# CABLE_MOTOR_DRIVERS.net
KiCad netlist of a schematic drawn in Altium Designer
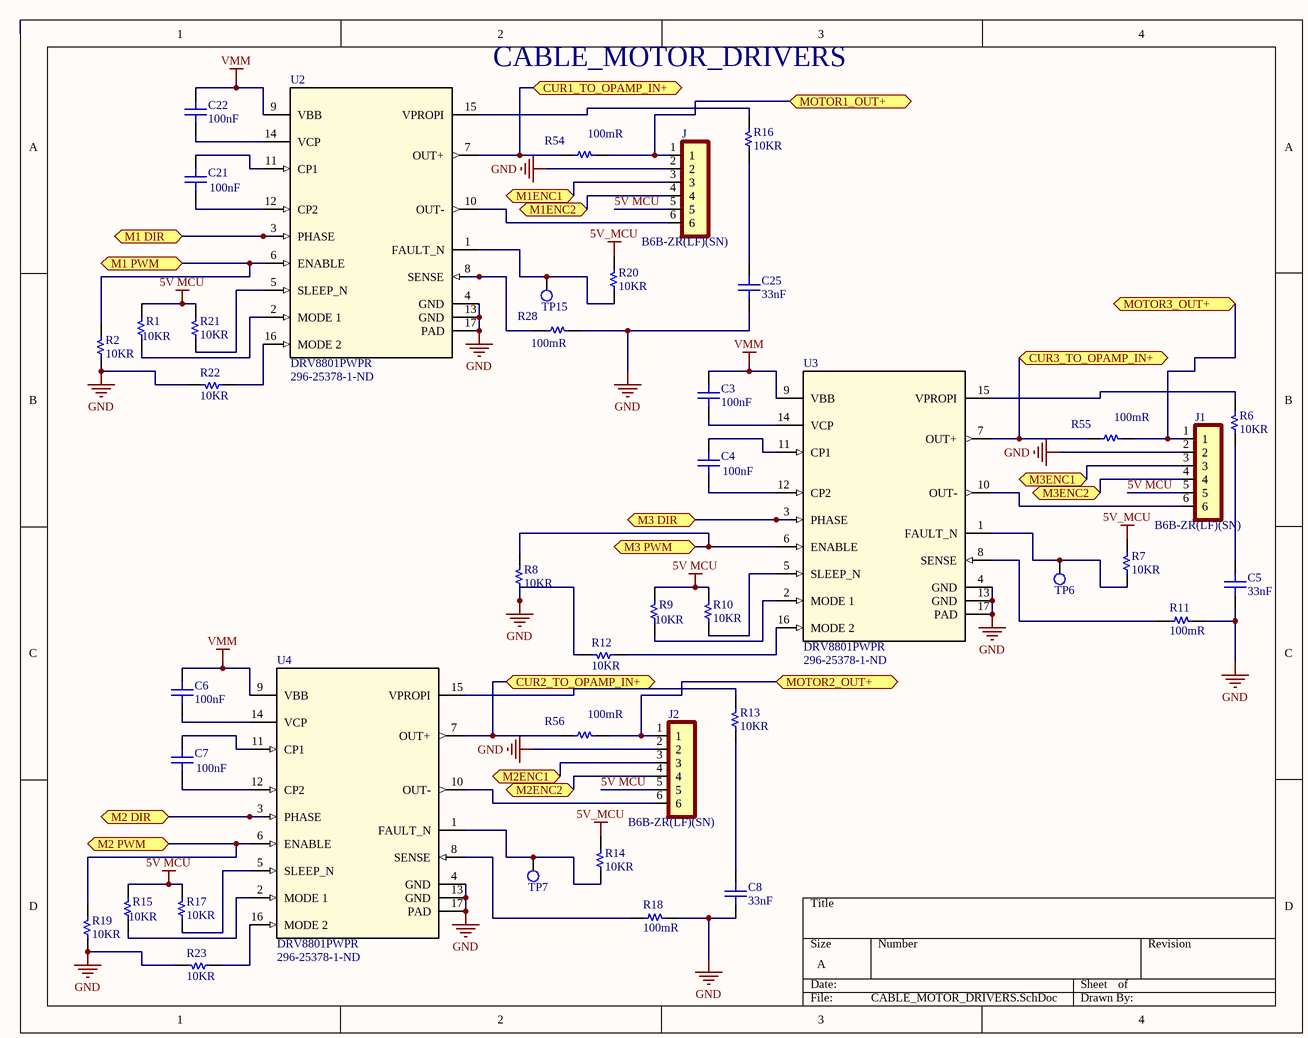
[diagram p0: CABLE_MOTOR_DRIVERS.SchDoc]

(export (version "E")
  (design (tool "Eeschema 10.0.6"))
  (components
    (comp (ref "C3")
      (value "100nF")
      (footprint "CAP_ADJ_0805")
      (description "CERAMIC CAPACITOR SMD 0805")
      (fields
        (field (name "MANUFACTURER") "KEMET")
        (field (name "MANUFACTURER PART NUMBER") "C0805C104J5RACAUTO")
      )
      (libsource (lib "ORI_MANIPULATOR_BRD") (part "CAP_ADJ_0805"))
    )
    (comp (ref "C4")
      (value "100nF")
      (footprint "CAP_ADJ_0805")
      (description "CERAMIC CAPACITOR SMD 0805")
      (fields
        (field (name "MANUFACTURER") "KEMET")
        (field (name "MANUFACTURER PART NUMBER") "C0805C104J5RACAUTO")
      )
      (libsource (lib "ORI_MANIPULATOR_BRD") (part "CAP_ADJ_0805"))
    )
    (comp (ref "C5")
      (value "33nF")
      (footprint "CAP_ADJ_0805")
      (description "CERAMIC CAPACITOR SMD 0805")
      (fields
        (field (name "MANUFACTURER") "Samsung")
        (field (name "MANUFACTURER PART NUMBER") "CL21B333JBANNNC")
      )
      (libsource (lib "ORI_MANIPULATOR_BRD") (part "CAP_ADJ_0805"))
    )
    (comp (ref "C6")
      (value "100nF")
      (footprint "CAP_ADJ_0805")
      (description "CERAMIC CAPACITOR SMD 0805")
      (fields
        (field (name "MANUFACTURER") "KEMET")
        (field (name "MANUFACTURER PART NUMBER") "C0805C104J5RACAUTO")
      )
      (libsource (lib "ORI_MANIPULATOR_BRD") (part "CAP_ADJ_0805"))
    )
    (comp (ref "C7")
      (value "100nF")
      (footprint "CAP_ADJ_0805")
      (description "CERAMIC CAPACITOR SMD 0805")
      (fields
        (field (name "MANUFACTURER") "KEMET")
        (field (name "MANUFACTURER PART NUMBER") "C0805C104J5RACAUTO")
      )
      (libsource (lib "ORI_MANIPULATOR_BRD") (part "CAP_ADJ_0805"))
    )
    (comp (ref "C8")
      (value "33nF")
      (footprint "CAP_ADJ_0805")
      (description "CERAMIC CAPACITOR SMD 0805")
      (fields
        (field (name "MANUFACTURER") "Samsung")
        (field (name "MANUFACTURER PART NUMBER") "CL21B333JBANNNC")
      )
      (libsource (lib "ORI_MANIPULATOR_BRD") (part "CAP_ADJ_0805"))
    )
    (comp (ref "C21")
      (value "100nF")
      (footprint "CAP_ADJ_0805")
      (description "CERAMIC CAPACITOR SMD 0805")
      (fields
        (field (name "MANUFACTURER") "KEMET")
        (field (name "MANUFACTURER PART NUMBER") "C0805C104J5RACAUTO")
      )
      (libsource (lib "ORI_MANIPULATOR_BRD") (part "CAP_ADJ_0805"))
    )
    (comp (ref "C22")
      (value "100nF")
      (footprint "CAP_ADJ_0805")
      (description "CERAMIC CAPACITOR SMD 0805")
      (fields
        (field (name "MANUFACTURER") "KEMET")
        (field (name "MANUFACTURER PART NUMBER") "C0805C104J5RACAUTO")
      )
      (libsource (lib "ORI_MANIPULATOR_BRD") (part "CAP_ADJ_0805"))
    )
    (comp (ref "C25")
      (value "33nF")
      (footprint "CAP_ADJ_0805")
      (description "CERAMIC CAPACITOR SMD 0805")
      (fields
        (field (name "MANUFACTURER") "Samsung")
        (field (name "MANUFACTURER PART NUMBER") "CL21B333JBANNNC")
      )
      (libsource (lib "ORI_MANIPULATOR_BRD") (part "CAP_ADJ_0805"))
    )
    (comp (ref "J")
      (value "B6B-ZR(LF)(SN)")
      (footprint "SnapEDApcb:JST_B6B-ZR(LF)(SN)")
      (description "Connector Header Through Hole 6 position 0.059 _1.50mm_")
      (fields (field (name "MF") "JST Sales") (field (name "MP") "B6B-ZR_LF__SN_"))
      (libsource (lib "SnapEDAsch") (part "B6B-ZR(LF)(SN)"))
    )
    (comp (ref "J1")
      (value "B6B-ZR(LF)(SN)")
      (footprint "SnapEDApcb:JST_B6B-ZR(LF)(SN)")
      (description "Connector Header Through Hole 6 position 0.059 _1.50mm_")
      (fields (field (name "MF") "JST Sales") (field (name "MP") "B6B-ZR_LF__SN_"))
      (libsource (lib "SnapEDAsch") (part "B6B-ZR(LF)(SN)"))
    )
    (comp (ref "J2")
      (value "B6B-ZR(LF)(SN)")
      (footprint "SnapEDApcb:JST_B6B-ZR(LF)(SN)")
      (description "Connector Header Through Hole 6 position 0.059 _1.50mm_")
      (fields (field (name "MF") "JST Sales") (field (name "MP") "B6B-ZR_LF__SN_"))
      (libsource (lib "SnapEDAsch") (part "B6B-ZR(LF)(SN)"))
    )
    (comp (ref "R1")
      (value "10KR")
      (footprint "RES_ADJ_0805_YAGEO")
      (description "RESISTOR 0805 YAGEO")
      (fields
        (field (name "MANUFACTURER") "Yageo")
        (field (name "MANUFACTURER PART NUMBER") "RC0805JR-0710KL")
      )
      (libsource (lib "ORI_MANIPULATOR_BRD") (part "RES_ADJ_0805"))
    )
    (comp (ref "R2")
      (value "10KR")
      (footprint "RES_ADJ_0805_YAGEO")
      (description "RESISTOR 0805 YAGEO")
      (fields
        (field (name "MANUFACTURER") "Yageo")
        (field (name "MANUFACTURER PART NUMBER") "RC0805JR-0710KL")
      )
      (libsource (lib "ORI_MANIPULATOR_BRD") (part "RES_ADJ_0805"))
    )
    (comp (ref "R6")
      (value "10KR")
      (footprint "RES_ADJ_0805_YAGEO")
      (description "RESISTOR 0805 YAGEO")
      (fields
        (field (name "MANUFACTURER") "Yageo")
        (field (name "MANUFACTURER PART NUMBER") "RC0805JR-0710KL")
      )
      (libsource (lib "ORI_MANIPULATOR_BRD") (part "RES_ADJ_0805"))
    )
    (comp (ref "R7")
      (value "10KR")
      (footprint "RES_ADJ_0805_YAGEO")
      (description "RESISTOR 0805 YAGEO")
      (fields
        (field (name "MANUFACTURER") "Yageo")
        (field (name "MANUFACTURER PART NUMBER") "RC0805JR-0710KL")
      )
      (libsource (lib "ORI_MANIPULATOR_BRD") (part "RES_ADJ_0805"))
    )
    (comp (ref "R8")
      (value "10KR")
      (footprint "RES_ADJ_0805_YAGEO")
      (description "RESISTOR 0805 YAGEO")
      (fields
        (field (name "MANUFACTURER") "Yageo")
        (field (name "MANUFACTURER PART NUMBER") "RC0805JR-0710KL")
      )
      (libsource (lib "ORI_MANIPULATOR_BRD") (part "RES_ADJ_0805"))
    )
    (comp (ref "R9")
      (value "10KR")
      (footprint "RES_ADJ_0805_YAGEO")
      (description "RESISTOR 0805 YAGEO")
      (fields
        (field (name "MANUFACTURER") "Yageo")
        (field (name "MANUFACTURER PART NUMBER") "RC0805JR-0710KL")
      )
      (libsource (lib "ORI_MANIPULATOR_BRD") (part "RES_ADJ_0805"))
    )
    (comp (ref "R10")
      (value "10KR")
      (footprint "RES_ADJ_0805_YAGEO")
      (description "RESISTOR 0805 YAGEO")
      (fields
        (field (name "MANUFACTURER") "Yageo")
        (field (name "MANUFACTURER PART NUMBER") "RC0805JR-0710KL")
      )
      (libsource (lib "ORI_MANIPULATOR_BRD") (part "RES_ADJ_0805"))
    )
    (comp (ref "R11")
      (value "100mR")
      (footprint "RES_ADJ_0805_YAGEO")
      (description "RESISTOR 0805 YAGEO")
      (fields
        (field (name "MANUFACTURER") "Panasonic")
        (field (name "MANUFACTURER PART NUMBER") "ERJ-6DSFR10V")
      )
      (libsource (lib "ORI_MANIPULATOR_BRD") (part "RES_ADJ_0805"))
    )
    (comp (ref "R12")
      (value "10KR")
      (footprint "RES_ADJ_0805_YAGEO")
      (description "RESISTOR 0805 YAGEO")
      (fields
        (field (name "MANUFACTURER") "Yageo")
        (field (name "MANUFACTURER PART NUMBER") "RC0805JR-0710KL")
      )
      (libsource (lib "ORI_MANIPULATOR_BRD") (part "RES_ADJ_0805"))
    )
    (comp (ref "R13")
      (value "10KR")
      (footprint "RES_ADJ_0805_YAGEO")
      (description "RESISTOR 0805 YAGEO")
      (fields
        (field (name "MANUFACTURER") "Yageo")
        (field (name "MANUFACTURER PART NUMBER") "RC0805JR-0710KL")
      )
      (libsource (lib "ORI_MANIPULATOR_BRD") (part "RES_ADJ_0805"))
    )
    (comp (ref "R14")
      (value "10KR")
      (footprint "RES_ADJ_0805_YAGEO")
      (description "RESISTOR 0805 YAGEO")
      (fields
        (field (name "MANUFACTURER") "Yageo")
        (field (name "MANUFACTURER PART NUMBER") "RC0805JR-0710KL")
      )
      (libsource (lib "ORI_MANIPULATOR_BRD") (part "RES_ADJ_0805"))
    )
    (comp (ref "R15")
      (value "10KR")
      (footprint "RES_ADJ_0805_YAGEO")
      (description "RESISTOR 0805 YAGEO")
      (fields
        (field (name "MANUFACTURER") "Yageo")
        (field (name "MANUFACTURER PART NUMBER") "RC0805JR-0710KL")
      )
      (libsource (lib "ORI_MANIPULATOR_BRD") (part "RES_ADJ_0805"))
    )
    (comp (ref "R16")
      (value "10KR")
      (footprint "RES_ADJ_0805_YAGEO")
      (description "RESISTOR 0805 YAGEO")
      (fields
        (field (name "MANUFACTURER") "Yageo")
        (field (name "MANUFACTURER PART NUMBER") "RC0805JR-0710KL")
      )
      (libsource (lib "ORI_MANIPULATOR_BRD") (part "RES_ADJ_0805"))
    )
    (comp (ref "R17")
      (value "10KR")
      (footprint "RES_ADJ_0805_YAGEO")
      (description "RESISTOR 0805 YAGEO")
      (fields
        (field (name "MANUFACTURER") "Yageo")
        (field (name "MANUFACTURER PART NUMBER") "RC0805JR-0710KL")
      )
      (libsource (lib "ORI_MANIPULATOR_BRD") (part "RES_ADJ_0805"))
    )
    (comp (ref "R18")
      (value "100mR")
      (footprint "RES_ADJ_0805_YAGEO")
      (description "RESISTOR 0805 YAGEO")
      (fields
        (field (name "MANUFACTURER") "Panasonic")
        (field (name "MANUFACTURER PART NUMBER") "ERJ-6DSFR10V")
      )
      (libsource (lib "ORI_MANIPULATOR_BRD") (part "RES_ADJ_0805"))
    )
    (comp (ref "R19")
      (value "10KR")
      (footprint "RES_ADJ_0805_YAGEO")
      (description "RESISTOR 0805 YAGEO")
      (fields
        (field (name "MANUFACTURER") "Yageo")
        (field (name "MANUFACTURER PART NUMBER") "RC0805JR-0710KL")
      )
      (libsource (lib "ORI_MANIPULATOR_BRD") (part "RES_ADJ_0805"))
    )
    (comp (ref "R20")
      (value "10KR")
      (footprint "RES_ADJ_0805_YAGEO")
      (description "RESISTOR 0805 YAGEO")
      (fields
        (field (name "MANUFACTURER") "Yageo")
        (field (name "MANUFACTURER PART NUMBER") "RC0805JR-0710KL")
      )
      (libsource (lib "ORI_MANIPULATOR_BRD") (part "RES_ADJ_0805"))
    )
    (comp (ref "R21")
      (value "10KR")
      (footprint "RES_ADJ_0805_YAGEO")
      (description "RESISTOR 0805 YAGEO")
      (fields
        (field (name "MANUFACTURER") "Yageo")
        (field (name "MANUFACTURER PART NUMBER") "RC0805JR-0710KL")
      )
      (libsource (lib "ORI_MANIPULATOR_BRD") (part "RES_ADJ_0805"))
    )
    (comp (ref "R22")
      (value "10KR")
      (footprint "RES_ADJ_0805_YAGEO")
      (description "RESISTOR 0805 YAGEO")
      (fields
        (field (name "MANUFACTURER") "Yageo")
        (field (name "MANUFACTURER PART NUMBER") "RC0805JR-0710KL")
      )
      (libsource (lib "ORI_MANIPULATOR_BRD") (part "RES_ADJ_0805"))
    )
    (comp (ref "R23")
      (value "10KR")
      (footprint "RES_ADJ_0805_YAGEO")
      (description "RESISTOR 0805 YAGEO")
      (fields
        (field (name "MANUFACTURER") "Yageo")
        (field (name "MANUFACTURER PART NUMBER") "RC0805JR-0710KL")
      )
      (libsource (lib "ORI_MANIPULATOR_BRD") (part "RES_ADJ_0805"))
    )
    (comp (ref "R28")
      (value "100mR")
      (footprint "RES_ADJ_0805_YAGEO")
      (description "RESISTOR 0805 YAGEO")
      (fields
        (field (name "MANUFACTURER") "Panasonic")
        (field (name "MANUFACTURER PART NUMBER") "ERJ-6DSFR10V")
      )
      (libsource (lib "ORI_MANIPULATOR_BRD") (part "RES_ADJ_0805"))
    )
    (comp (ref "R54")
      (value "100mR")
      (footprint "RES_ADJ_0805_YAGEO")
      (description "RESISTOR 0805 YAGEO")
      (fields
        (field (name "MANUFACTURER") "Panasonic")
        (field (name "MANUFACTURER PART NUMBER") "ERJ-6DSFR10V")
      )
      (libsource (lib "ORI_MANIPULATOR_BRD") (part "RES_ADJ_0805"))
    )
    (comp (ref "R55")
      (value "100mR")
      (footprint "RES_ADJ_0805_YAGEO")
      (description "RESISTOR 0805 YAGEO")
      (fields
        (field (name "MANUFACTURER") "Panasonic")
        (field (name "MANUFACTURER PART NUMBER") "ERJ-6DSFR10V")
      )
      (libsource (lib "ORI_MANIPULATOR_BRD") (part "RES_ADJ_0805"))
    )
    (comp (ref "R56")
      (value "100mR")
      (footprint "RES_ADJ_0805_YAGEO")
      (description "RESISTOR 0805 YAGEO")
      (fields
        (field (name "MANUFACTURER") "Panasonic")
        (field (name "MANUFACTURER PART NUMBER") "ERJ-6DSFR10V")
      )
      (libsource (lib "ORI_MANIPULATOR_BRD") (part "RES_ADJ_0805"))
    )
    (comp (ref "TP6")
      (value "TEST_POINT")
      (footprint "TEST_POINT")
      (description "TEST POINT PAD")
      (libsource (lib "ORI_MANIPULATOR_BRD") (part "TEST_POINT"))
    )
    (comp (ref "TP7")
      (value "TEST_POINT")
      (footprint "TEST_POINT")
      (description "TEST POINT PAD")
      (libsource (lib "ORI_MANIPULATOR_BRD") (part "TEST_POINT"))
    )
    (comp (ref "TP15")
      (value "TEST_POINT")
      (footprint "TEST_POINT")
      (description "TEST POINT PAD")
      (libsource (lib "ORI_MANIPULATOR_BRD") (part "TEST_POINT"))
    )
    (comp (ref "U2")
      (value "DRV8801PWPR")
      (footprint "PWP0016B_N")
      (description "IC MOTOR DRIVER PAR 16HTSSOP")
      (fields
        (field (name "MANUFACTURER") "Texas Instruments")
        (field (name "SUPPLIER PART NUMBER 1") "296-25378-1-ND")
      )
      (libsource (lib "ORI_MANIPULATOR_BRD") (part "DRV8801PWPR"))
    )
    (comp (ref "U3")
      (value "DRV8801PWPR")
      (footprint "PWP0016B_N")
      (description "IC MOTOR DRIVER PAR 16HTSSOP")
      (fields
        (field (name "MANUFACTURER") "Texas Instruments")
        (field (name "SUPPLIER PART NUMBER 1") "296-25378-1-ND")
      )
      (libsource (lib "ORI_MANIPULATOR_BRD") (part "DRV8801PWPR"))
    )
    (comp (ref "U4")
      (value "DRV8801PWPR")
      (footprint "PWP0016B_N")
      (description "IC MOTOR DRIVER PAR 16HTSSOP")
      (fields
        (field (name "MANUFACTURER") "Texas Instruments")
        (field (name "SUPPLIER PART NUMBER 1") "296-25378-1-ND")
      )
      (libsource (lib "ORI_MANIPULATOR_BRD") (part "DRV8801PWPR"))
    )
  )
  (nets
    (net (code "1") (name "/CUR1_TO_OPAMP_IN+") (class "Default")
      (node (ref "R54") (pin "1") (pinfunction "1_1") (pintype "passive"))
      (node (ref "U2") (pin "7") (pinfunction "OUT+_7") (pintype "output"))
    )
    (net (code "2") (name "/CUR2_TO_OPAMP_IN+") (class "Default")
      (node (ref "R56") (pin "1") (pinfunction "1_1") (pintype "passive"))
      (node (ref "U4") (pin "7") (pinfunction "OUT+_7") (pintype "output"))
    )
    (net (code "3") (name "/CUR3_TO_OPAMP_IN+") (class "Default")
      (node (ref "R55") (pin "1") (pinfunction "1_1") (pintype "passive"))
      (node (ref "U3") (pin "7") (pinfunction "OUT+_7") (pintype "output"))
    )
    (net (code "4") (name "/M1 DIR") (class "Default")
      (node (ref "U2") (pin "3") (pinfunction "PHASE_3") (pintype "input"))
    )
    (net (code "5") (name "/M1 PWM") (class "Default")
      (node (ref "R2") (pin "2") (pinfunction "2_2") (pintype "passive"))
      (node (ref "U2") (pin "6") (pinfunction "ENABLE_6") (pintype "input"))
    )
    (net (code "6") (name "/M1ENC1") (class "Default")
      (node (ref "J") (pin "3") (pinfunction "3_3") (pintype "passive"))
    )
    (net (code "7") (name "/M1ENC2") (class "Default")
      (node (ref "J") (pin "4") (pinfunction "4_4") (pintype "passive"))
    )
    (net (code "8") (name "/M2 DIR") (class "Default")
      (node (ref "U4") (pin "3") (pinfunction "PHASE_3") (pintype "input"))
    )
    (net (code "9") (name "/M2 PWM") (class "Default")
      (node (ref "R19") (pin "2") (pinfunction "2_2") (pintype "passive"))
      (node (ref "U4") (pin "6") (pinfunction "ENABLE_6") (pintype "input"))
    )
    (net (code "10") (name "/M2ENC1") (class "Default")
      (node (ref "J2") (pin "3") (pinfunction "3_3") (pintype "passive"))
    )
    (net (code "11") (name "/M2ENC2") (class "Default")
      (node (ref "J2") (pin "4") (pinfunction "4_4") (pintype "passive"))
    )
    (net (code "12") (name "/M3 DIR") (class "Default")
      (node (ref "U3") (pin "3") (pinfunction "PHASE_3") (pintype "input"))
    )
    (net (code "13") (name "/M3 PWM") (class "Default")
      (node (ref "R8") (pin "2") (pinfunction "2_2") (pintype "passive"))
      (node (ref "U3") (pin "6") (pinfunction "ENABLE_6") (pintype "input"))
    )
    (net (code "14") (name "/M3ENC1") (class "Default")
      (node (ref "J1") (pin "3") (pinfunction "3_3") (pintype "passive"))
    )
    (net (code "15") (name "/M3ENC2") (class "Default")
      (node (ref "J1") (pin "4") (pinfunction "4_4") (pintype "passive"))
    )
    (net (code "16") (name "/MOTOR1_OUT+") (class "Default")
      (node (ref "J") (pin "1") (pinfunction "1_1") (pintype "passive"))
      (node (ref "R54") (pin "2") (pinfunction "2_2") (pintype "passive"))
    )
    (net (code "17") (name "/MOTOR2_OUT+") (class "Default")
      (node (ref "J2") (pin "1") (pinfunction "1_1") (pintype "passive"))
      (node (ref "R56") (pin "2") (pinfunction "2_2") (pintype "passive"))
    )
    (net (code "18") (name "/MOTOR3_OUT+") (class "Default")
      (node (ref "J1") (pin "1") (pinfunction "1_1") (pintype "passive"))
      (node (ref "R55") (pin "2") (pinfunction "2_2") (pintype "passive"))
    )
    (net (code "19") (name "5V MCU") (class "Default")
      (node (ref "J") (pin "5") (pinfunction "5_5") (pintype "passive"))
      (node (ref "J1") (pin "5") (pinfunction "5_5") (pintype "passive"))
      (node (ref "J2") (pin "5") (pinfunction "5_5") (pintype "passive"))
      (node (ref "R1") (pin "2") (pinfunction "2_2") (pintype "passive"))
      (node (ref "R10") (pin "2") (pinfunction "2_2") (pintype "passive"))
      (node (ref "R15") (pin "2") (pinfunction "2_2") (pintype "passive"))
      (node (ref "R17") (pin "2") (pinfunction "2_2") (pintype "passive"))
      (node (ref "R21") (pin "2") (pinfunction "2_2") (pintype "passive"))
      (node (ref "R9") (pin "2") (pinfunction "2_2") (pintype "passive"))
    )
    (net (code "20") (name "5V_MCU") (class "Default")
      (node (ref "R14") (pin "2") (pinfunction "2_2") (pintype "passive"))
      (node (ref "R20") (pin "2") (pinfunction "2_2") (pintype "passive"))
      (node (ref "R7") (pin "2") (pinfunction "2_2") (pintype "passive"))
    )
    (net (code "21") (name "GND") (class "Default")
      (node (ref "C25") (pin "1") (pinfunction "1_1") (pintype "passive"))
      (node (ref "C5") (pin "1") (pinfunction "1_1") (pintype "passive"))
      (node (ref "C8") (pin "1") (pinfunction "1_1") (pintype "passive"))
      (node (ref "J") (pin "2") (pinfunction "2_2") (pintype "passive"))
      (node (ref "J1") (pin "2") (pinfunction "2_2") (pintype "passive"))
      (node (ref "J2") (pin "2") (pinfunction "2_2") (pintype "passive"))
      (node (ref "R11") (pin "2") (pinfunction "2_2") (pintype "passive"))
      (node (ref "R12") (pin "2") (pinfunction "2_2") (pintype "passive"))
      (node (ref "R18") (pin "2") (pinfunction "2_2") (pintype "passive"))
      (node (ref "R19") (pin "1") (pinfunction "1_1") (pintype "passive"))
      (node (ref "R2") (pin "1") (pinfunction "1_1") (pintype "passive"))
      (node (ref "R22") (pin "2") (pinfunction "2_2") (pintype "passive"))
      (node (ref "R23") (pin "2") (pinfunction "2_2") (pintype "passive"))
      (node (ref "R28") (pin "2") (pinfunction "2_2") (pintype "passive"))
      (node (ref "R8") (pin "1") (pinfunction "1_1") (pintype "passive"))
      (node (ref "U2") (pin "13") (pinfunction "GND_13") (pintype "power_in"))
      (node (ref "U2") (pin "17") (pinfunction "PAD_17") (pintype "power_in"))
      (node (ref "U2") (pin "4") (pinfunction "GND_4") (pintype "power_in"))
      (node (ref "U3") (pin "13") (pinfunction "GND_13") (pintype "power_in"))
      (node (ref "U3") (pin "17") (pinfunction "PAD_17") (pintype "power_in"))
      (node (ref "U3") (pin "4") (pinfunction "GND_4") (pintype "power_in"))
      (node (ref "U4") (pin "13") (pinfunction "GND_13") (pintype "power_in"))
      (node (ref "U4") (pin "17") (pinfunction "PAD_17") (pintype "power_in"))
      (node (ref "U4") (pin "4") (pinfunction "GND_4") (pintype "power_in"))
    )
    (net (code "22") (name "Net-(C5-Pad2)") (class "Default")
      (node (ref "C5") (pin "2") (pinfunction "2_2") (pintype "passive"))
      (node (ref "R6") (pin "1") (pinfunction "1_1") (pintype "passive"))
    )
    (net (code "23") (name "Net-(C8-Pad2)") (class "Default")
      (node (ref "C8") (pin "2") (pinfunction "2_2") (pintype "passive"))
      (node (ref "R13") (pin "1") (pinfunction "1_1") (pintype "passive"))
    )
    (net (code "24") (name "Net-(C25-Pad2)") (class "Default")
      (node (ref "C25") (pin "2") (pinfunction "2_2") (pintype "passive"))
      (node (ref "R16") (pin "1") (pinfunction "1_1") (pintype "passive"))
    )
    (net (code "25") (name "Net-(U2-CP1)") (class "Default")
      (node (ref "C21") (pin "2") (pinfunction "2_2") (pintype "passive"))
      (node (ref "U2") (pin "11") (pinfunction "CP1_11") (pintype "input"))
    )
    (net (code "26") (name "Net-(U2-CP2)") (class "Default")
      (node (ref "C21") (pin "1") (pinfunction "1_1") (pintype "passive"))
      (node (ref "U2") (pin "12") (pinfunction "CP2_12") (pintype "input"))
    )
    (net (code "27") (name "Net-(U2-FAULT_N)") (class "Default")
      (node (ref "R20") (pin "1") (pinfunction "1_1") (pintype "passive"))
      (node (ref "TP15") (pin "1") (pinfunction "1_1") (pintype "passive"))
      (node (ref "U2") (pin "1") (pinfunction "FAULT_N_1") (pintype "open_collector"))
    )
    (net (code "28") (name "Net-(U2-MODE_1)") (class "Default")
      (node (ref "R1") (pin "1") (pinfunction "1_1") (pintype "passive"))
      (node (ref "U2") (pin "2") (pinfunction "MODE_1_2") (pintype "input"))
    )
    (net (code "29") (name "Net-(U2-MODE_2)") (class "Default")
      (node (ref "R22") (pin "1") (pinfunction "1_1") (pintype "passive"))
      (node (ref "U2") (pin "16") (pinfunction "MODE_2_16") (pintype "input"))
    )
    (net (code "30") (name "Net-(U2-OUT-)") (class "Default")
      (node (ref "J") (pin "6") (pinfunction "6_6") (pintype "passive"))
      (node (ref "U2") (pin "10") (pinfunction "OUT-_10") (pintype "output"))
    )
    (net (code "31") (name "Net-(U2-SENSE)") (class "Default")
      (node (ref "R28") (pin "1") (pinfunction "1_1") (pintype "passive"))
      (node (ref "U2") (pin "8") (pinfunction "SENSE_8") (pintype "input"))
    )
    (net (code "32") (name "Net-(U2-SLEEP_N)") (class "Default")
      (node (ref "R21") (pin "1") (pinfunction "1_1") (pintype "passive"))
      (node (ref "U2") (pin "5") (pinfunction "SLEEP_N_5") (pintype "input"))
    )
    (net (code "33") (name "Net-(U2-VCP)") (class "Default")
      (node (ref "C22") (pin "1") (pinfunction "1_1") (pintype "passive"))
      (node (ref "U2") (pin "14") (pinfunction "VCP_14") (pintype "passive"))
    )
    (net (code "34") (name "Net-(U2-VPROPI)") (class "Default")
      (node (ref "R16") (pin "2") (pinfunction "2_2") (pintype "passive"))
      (node (ref "U2") (pin "15") (pinfunction "VPROPI_15") (pintype "power_in"))
    )
    (net (code "35") (name "Net-(U3-CP1)") (class "Default")
      (node (ref "C4") (pin "2") (pinfunction "2_2") (pintype "passive"))
      (node (ref "U3") (pin "11") (pinfunction "CP1_11") (pintype "input"))
    )
    (net (code "36") (name "Net-(U3-CP2)") (class "Default")
      (node (ref "C4") (pin "1") (pinfunction "1_1") (pintype "passive"))
      (node (ref "U3") (pin "12") (pinfunction "CP2_12") (pintype "input"))
    )
    (net (code "37") (name "Net-(U3-FAULT_N)") (class "Default")
      (node (ref "R7") (pin "1") (pinfunction "1_1") (pintype "passive"))
      (node (ref "TP6") (pin "1") (pinfunction "1_1") (pintype "passive"))
      (node (ref "U3") (pin "1") (pinfunction "FAULT_N_1") (pintype "open_collector"))
    )
    (net (code "38") (name "Net-(U3-MODE_1)") (class "Default")
      (node (ref "R9") (pin "1") (pinfunction "1_1") (pintype "passive"))
      (node (ref "U3") (pin "2") (pinfunction "MODE_1_2") (pintype "input"))
    )
    (net (code "39") (name "Net-(U3-MODE_2)") (class "Default")
      (node (ref "R12") (pin "1") (pinfunction "1_1") (pintype "passive"))
      (node (ref "U3") (pin "16") (pinfunction "MODE_2_16") (pintype "input"))
    )
    (net (code "40") (name "Net-(U3-OUT-)") (class "Default")
      (node (ref "J1") (pin "6") (pinfunction "6_6") (pintype "passive"))
      (node (ref "U3") (pin "10") (pinfunction "OUT-_10") (pintype "output"))
    )
    (net (code "41") (name "Net-(U3-SENSE)") (class "Default")
      (node (ref "R11") (pin "1") (pinfunction "1_1") (pintype "passive"))
      (node (ref "U3") (pin "8") (pinfunction "SENSE_8") (pintype "input"))
    )
    (net (code "42") (name "Net-(U3-SLEEP_N)") (class "Default")
      (node (ref "R10") (pin "1") (pinfunction "1_1") (pintype "passive"))
      (node (ref "U3") (pin "5") (pinfunction "SLEEP_N_5") (pintype "input"))
    )
    (net (code "43") (name "Net-(U3-VCP)") (class "Default")
      (node (ref "C3") (pin "1") (pinfunction "1_1") (pintype "passive"))
      (node (ref "U3") (pin "14") (pinfunction "VCP_14") (pintype "passive"))
    )
    (net (code "44") (name "Net-(U3-VPROPI)") (class "Default")
      (node (ref "R6") (pin "2") (pinfunction "2_2") (pintype "passive"))
      (node (ref "U3") (pin "15") (pinfunction "VPROPI_15") (pintype "power_in"))
    )
    (net (code "45") (name "Net-(U4-CP1)") (class "Default")
      (node (ref "C7") (pin "2") (pinfunction "2_2") (pintype "passive"))
      (node (ref "U4") (pin "11") (pinfunction "CP1_11") (pintype "input"))
    )
    (net (code "46") (name "Net-(U4-CP2)") (class "Default")
      (node (ref "C7") (pin "1") (pinfunction "1_1") (pintype "passive"))
      (node (ref "U4") (pin "12") (pinfunction "CP2_12") (pintype "input"))
    )
    (net (code "47") (name "Net-(U4-FAULT_N)") (class "Default")
      (node (ref "R14") (pin "1") (pinfunction "1_1") (pintype "passive"))
      (node (ref "TP7") (pin "1") (pinfunction "1_1") (pintype "passive"))
      (node (ref "U4") (pin "1") (pinfunction "FAULT_N_1") (pintype "open_collector"))
    )
    (net (code "48") (name "Net-(U4-MODE_1)") (class "Default")
      (node (ref "R15") (pin "1") (pinfunction "1_1") (pintype "passive"))
      (node (ref "U4") (pin "2") (pinfunction "MODE_1_2") (pintype "input"))
    )
    (net (code "49") (name "Net-(U4-MODE_2)") (class "Default")
      (node (ref "R23") (pin "1") (pinfunction "1_1") (pintype "passive"))
      (node (ref "U4") (pin "16") (pinfunction "MODE_2_16") (pintype "input"))
    )
    (net (code "50") (name "Net-(U4-OUT-)") (class "Default")
      (node (ref "J2") (pin "6") (pinfunction "6_6") (pintype "passive"))
      (node (ref "U4") (pin "10") (pinfunction "OUT-_10") (pintype "output"))
    )
    (net (code "51") (name "Net-(U4-SENSE)") (class "Default")
      (node (ref "R18") (pin "1") (pinfunction "1_1") (pintype "passive"))
      (node (ref "U4") (pin "8") (pinfunction "SENSE_8") (pintype "input"))
    )
    (net (code "52") (name "Net-(U4-SLEEP_N)") (class "Default")
      (node (ref "R17") (pin "1") (pinfunction "1_1") (pintype "passive"))
      (node (ref "U4") (pin "5") (pinfunction "SLEEP_N_5") (pintype "input"))
    )
    (net (code "53") (name "Net-(U4-VCP)") (class "Default")
      (node (ref "C6") (pin "1") (pinfunction "1_1") (pintype "passive"))
      (node (ref "U4") (pin "14") (pinfunction "VCP_14") (pintype "passive"))
    )
    (net (code "54") (name "Net-(U4-VPROPI)") (class "Default")
      (node (ref "R13") (pin "2") (pinfunction "2_2") (pintype "passive"))
      (node (ref "U4") (pin "15") (pinfunction "VPROPI_15") (pintype "power_in"))
    )
    (net (code "55") (name "VMM") (class "Default")
      (node (ref "C22") (pin "2") (pinfunction "2_2") (pintype "passive"))
      (node (ref "C3") (pin "2") (pinfunction "2_2") (pintype "passive"))
      (node (ref "C6") (pin "2") (pinfunction "2_2") (pintype "passive"))
      (node (ref "U2") (pin "9") (pinfunction "VBB_9") (pintype "power_in"))
      (node (ref "U3") (pin "9") (pinfunction "VBB_9") (pintype "power_in"))
      (node (ref "U4") (pin "9") (pinfunction "VBB_9") (pintype "power_in"))
    )
  )
)
